# Schematics.net
KiCad netlist of a schematic drawn in Altium Designer
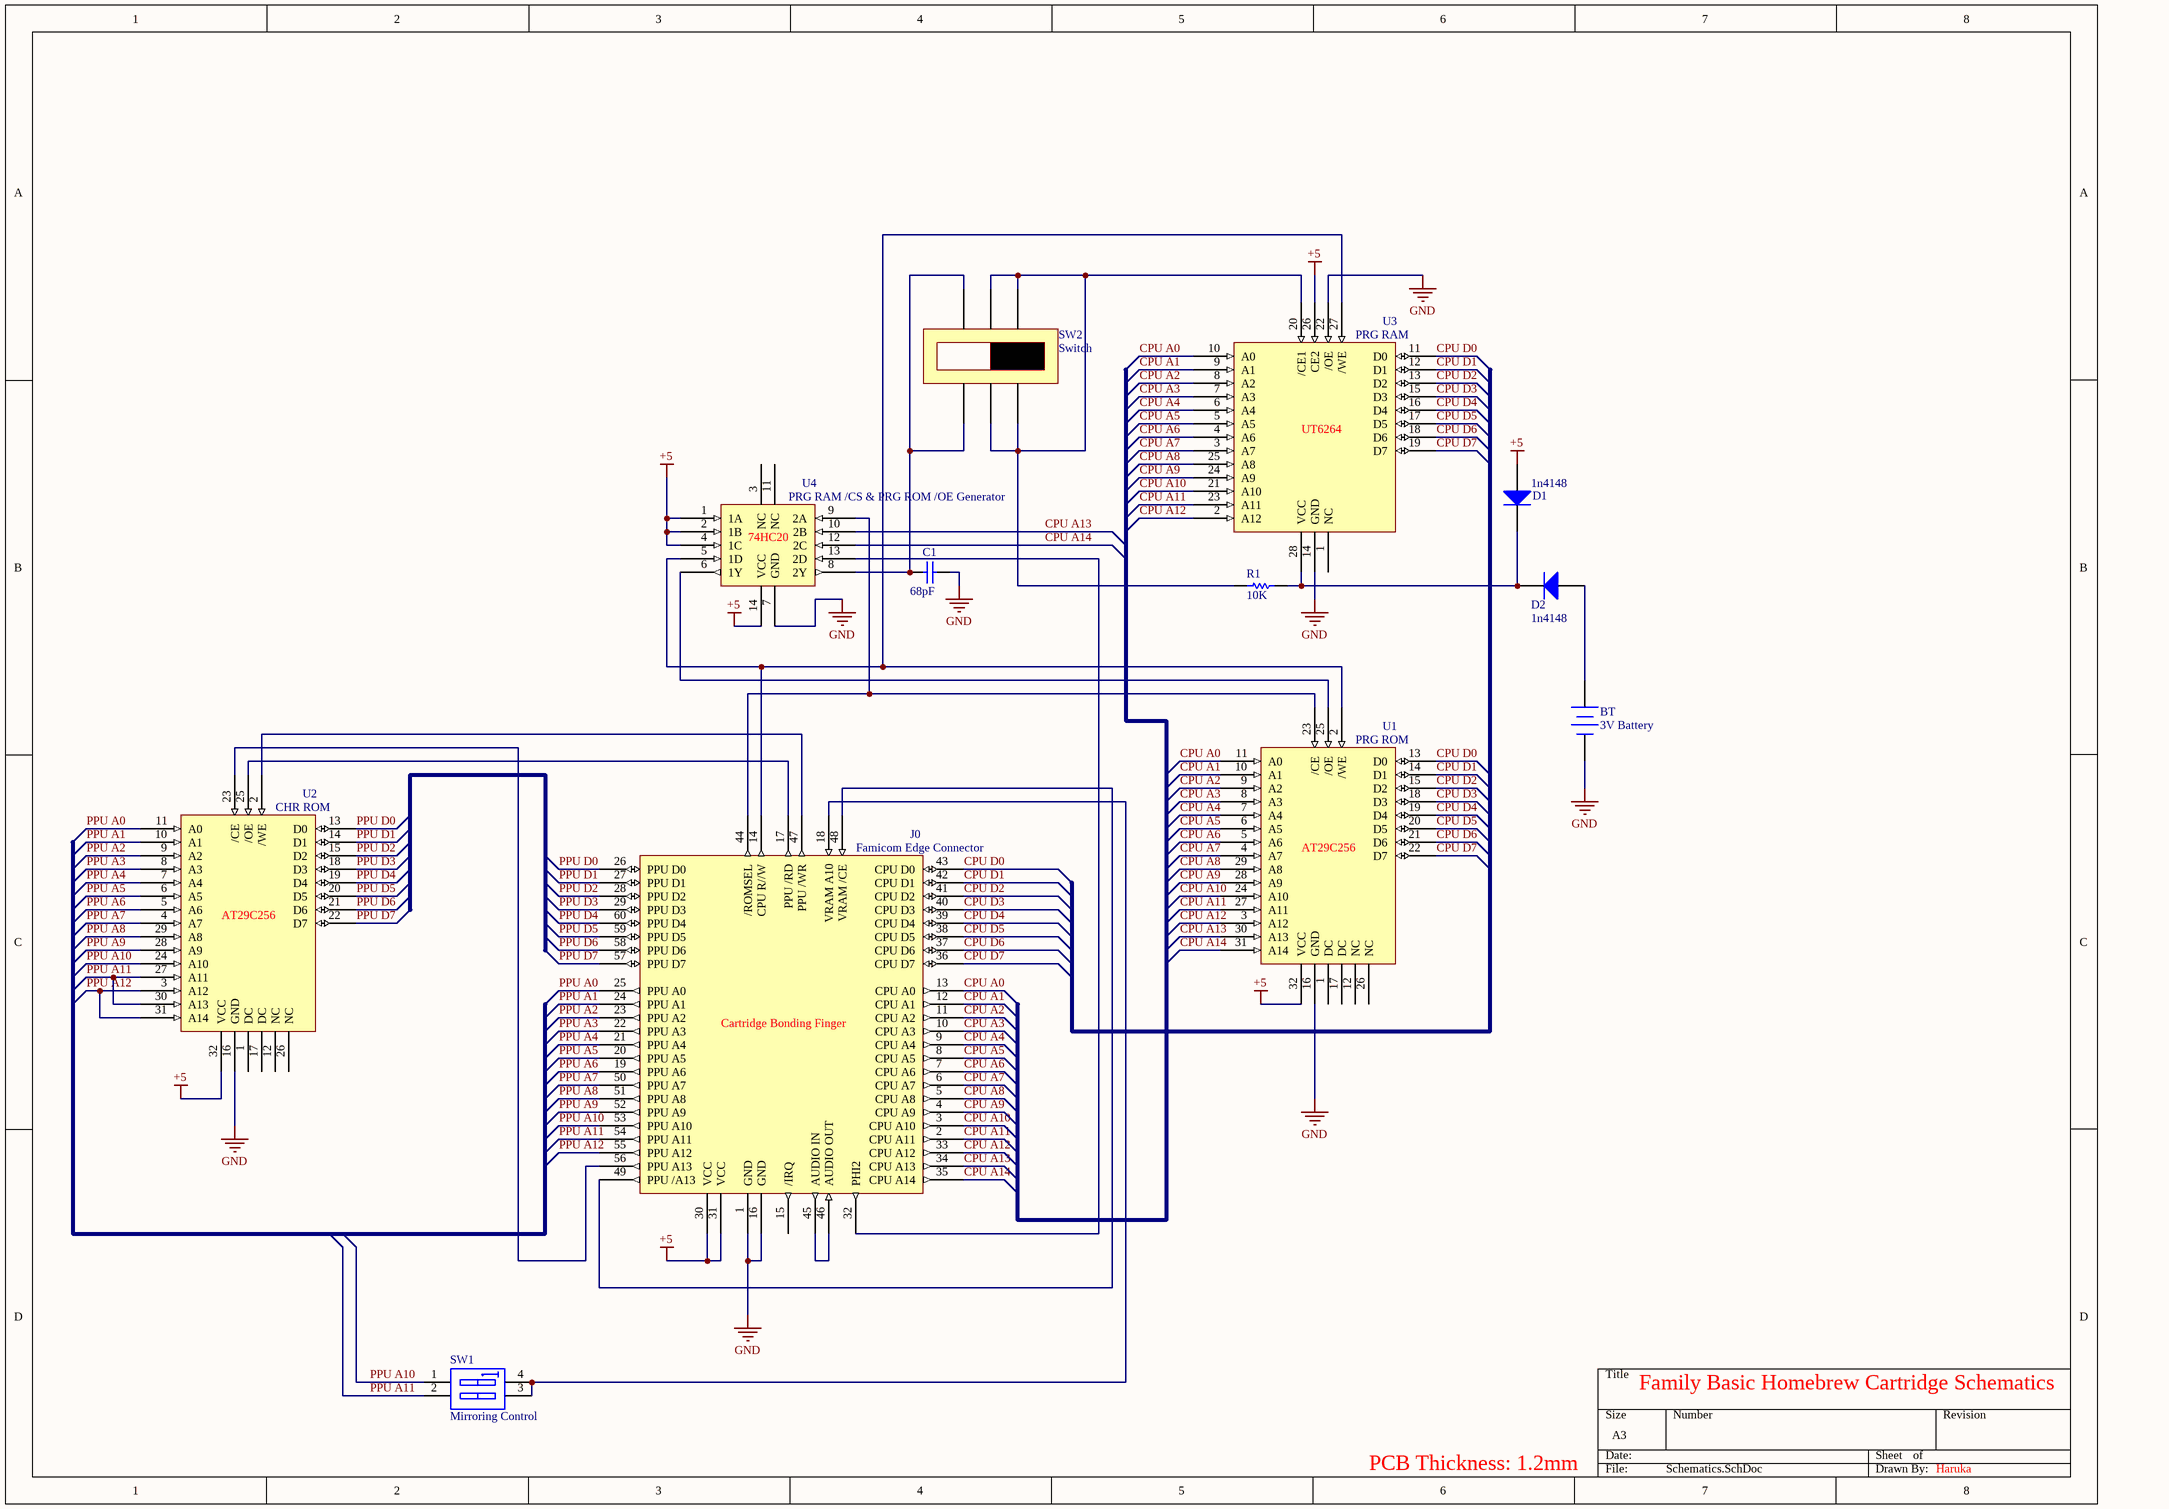
[diagram p0: Schematics.SchDoc]

(export (version "E")
  (design (tool "Eeschema 10.0.6"))
  (components
    (comp (ref "BT")
      (value "3V Battery")
      (footprint "BAT-2")
      (description "Multicell Battery")
      (fields (field (name "PUBLISHER") "Altium Limited"))
      (libsource (lib "Miscellaneous Devices") (part "Battery"))
    )
    (comp (ref "C1")
      (value "68pF")
      (footprint "C2512")
      (description "Capacitor (Semiconductor SIM Model)")
      (fields (field (name "Comment") "Cap Semi") (field (name "PUBLISHER") "Altium Limited"))
      (libsource (lib "Miscellaneous Devices") (part "Cap Semi"))
    )
    (comp (ref "D1")
      (value "1n4148")
      (footprint "DO-35")
      (description "High Conductance Fast Diode")
      (fields (field (name "PUBLISHER") "Altium Limited"))
      (libsource (lib "Miscellaneous Devices") (part "Diode 1N4148"))
    )
    (comp (ref "D2")
      (value "1n4148")
      (footprint "DO-35")
      (description "High Conductance Fast Diode")
      (fields (field (name "PUBLISHER") "Altium Limited"))
      (libsource (lib "Miscellaneous Devices") (part "Diode 1N4148"))
    )
    (comp (ref "J0")
      (value "Famicom Edge Connector")
      (footprint "CartridgeBondingFinger")
      (libsource (lib "CartridgeBondingFinger") (part "CartridgeBondingFinger"))
    )
    (comp (ref "R1")
      (value "10K")
      (footprint "AXIAL-0.3")
      (description "Resistor")
      (fields (field (name "Comment") "Res1") (field (name "PUBLISHER") "Altium Limited"))
      (libsource (lib "Miscellaneous Devices") (part "Res1"))
    )
    (comp (ref "SW1")
      (value "Mirroring Control")
      (footprint "DIP-4")
      (description "DIP Switch, 2 Position, SPST")
      (fields (field (name "PUBLISHER") "Altium Limited"))
      (libsource (lib "Miscellaneous Devices") (part "SW DIP-2"))
    )
    (comp (ref "SW2") (value "Switch") (footprint "DPDT-6") (libsource (lib "Discrete") (part "Switch")))
    (comp (ref "U1") (value "PRG ROM") (footprint "PLCC32") (libsource (lib "AT29C256") (part "AT29C256")))
    (comp (ref "U2") (value "CHR ROM") (footprint "PLCC32") (libsource (lib "AT29C256") (part "AT29C256")))
    (comp (ref "U3")
      (value "PRG RAM")
      (footprint "SOP127P1207-28N")
      (libsource (lib "UT6264") (part "UT6264"))
    )
    (comp (ref "U4")
      (value "PRG RAM /CS & PRG ROM /OE Generator")
      (footprint "SOP127P636-14N")
      (libsource (lib "74HC20") (part "74HC20"))
    )
  )
  (nets
    (net (code "1") (name "+5") (class "Default")
      (node (ref "D1") (pin "1") (pinfunction "A_1") (pintype "passive"))
      (node (ref "J0") (pin "30") (pinfunction "VCC_30") (pintype "power_in"))
      (node (ref "J0") (pin "31") (pinfunction "VCC_31") (pintype "power_in"))
      (node (ref "U1") (pin "32") (pinfunction "VCC_32") (pintype "power_in"))
      (node (ref "U2") (pin "32") (pinfunction "VCC_32") (pintype "power_in"))
      (node (ref "U3") (pin "26") (pinfunction "CE2_26") (pintype "input"))
      (node (ref "U4") (pin "1") (pinfunction "1A_1") (pintype "input"))
      (node (ref "U4") (pin "14") (pinfunction "VCC_14") (pintype "power_in"))
      (node (ref "U4") (pin "2") (pinfunction "1B_2") (pintype "input"))
      (node (ref "U4") (pin "4") (pinfunction "1C_4") (pintype "input"))
    )
    (net (code "2") (name "/CPU A0") (class "Default")
      (node (ref "J0") (pin "13") (pinfunction "CPU_A0_13") (pintype "output"))
      (node (ref "U1") (pin "11") (pinfunction "A0_11") (pintype "input"))
      (node (ref "U3") (pin "10") (pinfunction "A0_10") (pintype "input"))
    )
    (net (code "3") (name "/CPU A1") (class "Default")
      (node (ref "J0") (pin "12") (pinfunction "CPU_A1_12") (pintype "output"))
      (node (ref "U1") (pin "10") (pinfunction "A1_10") (pintype "input"))
      (node (ref "U3") (pin "9") (pinfunction "A1_9") (pintype "input"))
    )
    (net (code "4") (name "/CPU A2") (class "Default")
      (node (ref "J0") (pin "11") (pinfunction "CPU_A2_11") (pintype "output"))
      (node (ref "U1") (pin "9") (pinfunction "A2_9") (pintype "input"))
      (node (ref "U3") (pin "8") (pinfunction "A2_8") (pintype "input"))
    )
    (net (code "5") (name "/CPU A3") (class "Default")
      (node (ref "J0") (pin "10") (pinfunction "CPU_A3_10") (pintype "output"))
      (node (ref "U1") (pin "8") (pinfunction "A3_8") (pintype "input"))
      (node (ref "U3") (pin "7") (pinfunction "A3_7") (pintype "input"))
    )
    (net (code "6") (name "/CPU A4") (class "Default")
      (node (ref "J0") (pin "9") (pinfunction "CPU_A4_9") (pintype "output"))
      (node (ref "U1") (pin "7") (pinfunction "A4_7") (pintype "input"))
      (node (ref "U3") (pin "6") (pinfunction "A4_6") (pintype "input"))
    )
    (net (code "7") (name "/CPU A5") (class "Default")
      (node (ref "J0") (pin "8") (pinfunction "CPU_A5_8") (pintype "output"))
      (node (ref "U1") (pin "6") (pinfunction "A5_6") (pintype "input"))
      (node (ref "U3") (pin "5") (pinfunction "A5_5") (pintype "input"))
    )
    (net (code "8") (name "/CPU A6") (class "Default")
      (node (ref "J0") (pin "7") (pinfunction "CPU_A6_7") (pintype "output"))
      (node (ref "U1") (pin "5") (pinfunction "A6_5") (pintype "input"))
      (node (ref "U3") (pin "4") (pinfunction "A6_4") (pintype "input"))
    )
    (net (code "9") (name "/CPU A7") (class "Default")
      (node (ref "J0") (pin "6") (pinfunction "CPU_A7_6") (pintype "output"))
      (node (ref "U1") (pin "4") (pinfunction "A7_4") (pintype "input"))
      (node (ref "U3") (pin "3") (pinfunction "A7_3") (pintype "input"))
    )
    (net (code "10") (name "/CPU A8") (class "Default")
      (node (ref "J0") (pin "5") (pinfunction "CPU_A8_5") (pintype "output"))
      (node (ref "U1") (pin "29") (pinfunction "A8_29") (pintype "input"))
      (node (ref "U3") (pin "25") (pinfunction "A8_25") (pintype "input"))
    )
    (net (code "11") (name "/CPU A9") (class "Default")
      (node (ref "J0") (pin "4") (pinfunction "CPU_A9_4") (pintype "output"))
      (node (ref "U1") (pin "28") (pinfunction "A9_28") (pintype "input"))
      (node (ref "U3") (pin "24") (pinfunction "A9_24") (pintype "input"))
    )
    (net (code "12") (name "/CPU A10") (class "Default")
      (node (ref "J0") (pin "3") (pinfunction "CPU_A10_3") (pintype "output"))
      (node (ref "U1") (pin "24") (pinfunction "A10_24") (pintype "input"))
      (node (ref "U3") (pin "21") (pinfunction "A10_21") (pintype "input"))
    )
    (net (code "13") (name "/CPU A11") (class "Default")
      (node (ref "J0") (pin "2") (pinfunction "CPU_A11_2") (pintype "output"))
      (node (ref "U1") (pin "27") (pinfunction "A11_27") (pintype "input"))
      (node (ref "U3") (pin "23") (pinfunction "A11_23") (pintype "input"))
    )
    (net (code "14") (name "/CPU A12") (class "Default")
      (node (ref "J0") (pin "33") (pinfunction "CPU_A12_33") (pintype "output"))
      (node (ref "U1") (pin "3") (pinfunction "A12_3") (pintype "input"))
      (node (ref "U3") (pin "2") (pinfunction "A12_2") (pintype "input"))
    )
    (net (code "15") (name "/CPU A13") (class "Default")
      (node (ref "J0") (pin "34") (pinfunction "CPU_A13_34") (pintype "output"))
      (node (ref "U1") (pin "30") (pinfunction "A13_30") (pintype "input"))
      (node (ref "U4") (pin "10") (pinfunction "2B_10") (pintype "input"))
    )
    (net (code "16") (name "/CPU A14") (class "Default")
      (node (ref "J0") (pin "35") (pinfunction "CPU_A14_35") (pintype "output"))
      (node (ref "U1") (pin "31") (pinfunction "A14_31") (pintype "input"))
      (node (ref "U4") (pin "12") (pinfunction "2C_12") (pintype "input"))
    )
    (net (code "17") (name "/CPU D0") (class "Default")
      (node (ref "J0") (pin "43") (pinfunction "CPU_D0_43") (pintype "bidirectional"))
      (node (ref "U1") (pin "13") (pinfunction "D0_13") (pintype "bidirectional"))
      (node (ref "U3") (pin "11") (pinfunction "D0_11") (pintype "bidirectional"))
    )
    (net (code "18") (name "/CPU D1") (class "Default")
      (node (ref "J0") (pin "42") (pinfunction "CPU_D1_42") (pintype "bidirectional"))
      (node (ref "U1") (pin "14") (pinfunction "D1_14") (pintype "bidirectional"))
      (node (ref "U3") (pin "12") (pinfunction "D1_12") (pintype "bidirectional"))
    )
    (net (code "19") (name "/CPU D2") (class "Default")
      (node (ref "J0") (pin "41") (pinfunction "CPU_D2_41") (pintype "bidirectional"))
      (node (ref "U1") (pin "15") (pinfunction "D2_15") (pintype "bidirectional"))
      (node (ref "U3") (pin "13") (pinfunction "D2_13") (pintype "bidirectional"))
    )
    (net (code "20") (name "/CPU D3") (class "Default")
      (node (ref "J0") (pin "40") (pinfunction "CPU_D3_40") (pintype "bidirectional"))
      (node (ref "U1") (pin "18") (pinfunction "D3_18") (pintype "bidirectional"))
      (node (ref "U3") (pin "15") (pinfunction "D3_15") (pintype "bidirectional"))
    )
    (net (code "21") (name "/CPU D4") (class "Default")
      (node (ref "J0") (pin "39") (pinfunction "CPU_D4_39") (pintype "bidirectional"))
      (node (ref "U1") (pin "19") (pinfunction "D4_19") (pintype "bidirectional"))
      (node (ref "U3") (pin "16") (pinfunction "D4_16") (pintype "bidirectional"))
    )
    (net (code "22") (name "/CPU D5") (class "Default")
      (node (ref "J0") (pin "38") (pinfunction "CPU_D5_38") (pintype "bidirectional"))
      (node (ref "U1") (pin "20") (pinfunction "D5_20") (pintype "bidirectional"))
      (node (ref "U3") (pin "17") (pinfunction "D5_17") (pintype "bidirectional"))
    )
    (net (code "23") (name "/CPU D6") (class "Default")
      (node (ref "J0") (pin "37") (pinfunction "CPU_D6_37") (pintype "bidirectional"))
      (node (ref "U1") (pin "21") (pinfunction "D6_21") (pintype "bidirectional"))
      (node (ref "U3") (pin "18") (pinfunction "D6_18") (pintype "bidirectional"))
    )
    (net (code "24") (name "/CPU D7") (class "Default")
      (node (ref "J0") (pin "36") (pinfunction "CPU_D7_36") (pintype "bidirectional"))
      (node (ref "U1") (pin "22") (pinfunction "D7_22") (pintype "bidirectional"))
      (node (ref "U3") (pin "19") (pinfunction "D7_19") (pintype "bidirectional"))
    )
    (net (code "25") (name "/PPU A0") (class "Default")
      (node (ref "J0") (pin "25") (pinfunction "PPU_A0_25") (pintype "output"))
      (node (ref "U2") (pin "11") (pinfunction "A0_11") (pintype "input"))
    )
    (net (code "26") (name "/PPU A1") (class "Default")
      (node (ref "J0") (pin "24") (pinfunction "PPU_A1_24") (pintype "output"))
      (node (ref "U2") (pin "10") (pinfunction "A1_10") (pintype "input"))
    )
    (net (code "27") (name "/PPU A2") (class "Default")
      (node (ref "J0") (pin "23") (pinfunction "PPU_A2_23") (pintype "output"))
      (node (ref "U2") (pin "9") (pinfunction "A2_9") (pintype "input"))
    )
    (net (code "28") (name "/PPU A3") (class "Default")
      (node (ref "J0") (pin "22") (pinfunction "PPU_A3_22") (pintype "output"))
      (node (ref "U2") (pin "8") (pinfunction "A3_8") (pintype "input"))
    )
    (net (code "29") (name "/PPU A4") (class "Default")
      (node (ref "J0") (pin "21") (pinfunction "PPU_A4_21") (pintype "output"))
      (node (ref "U2") (pin "7") (pinfunction "A4_7") (pintype "input"))
    )
    (net (code "30") (name "/PPU A5") (class "Default")
      (node (ref "J0") (pin "20") (pinfunction "PPU_A5_20") (pintype "output"))
      (node (ref "U2") (pin "6") (pinfunction "A5_6") (pintype "input"))
    )
    (net (code "31") (name "/PPU A6") (class "Default")
      (node (ref "J0") (pin "19") (pinfunction "PPU_A6_19") (pintype "output"))
      (node (ref "U2") (pin "5") (pinfunction "A6_5") (pintype "input"))
    )
    (net (code "32") (name "/PPU A7") (class "Default")
      (node (ref "J0") (pin "50") (pinfunction "PPU_A7_50") (pintype "output"))
      (node (ref "U2") (pin "4") (pinfunction "A7_4") (pintype "input"))
    )
    (net (code "33") (name "/PPU A8") (class "Default")
      (node (ref "J0") (pin "51") (pinfunction "PPU_A8_51") (pintype "output"))
      (node (ref "U2") (pin "29") (pinfunction "A8_29") (pintype "input"))
    )
    (net (code "34") (name "/PPU A9") (class "Default")
      (node (ref "J0") (pin "52") (pinfunction "PPU_A9_52") (pintype "output"))
      (node (ref "U2") (pin "28") (pinfunction "A9_28") (pintype "input"))
    )
    (net (code "35") (name "/PPU A10") (class "Default")
      (node (ref "J0") (pin "53") (pinfunction "PPU_A10_53") (pintype "output"))
      (node (ref "SW1") (pin "1") (pinfunction "A1_1") (pintype "passive"))
      (node (ref "U2") (pin "24") (pinfunction "A10_24") (pintype "input"))
    )
    (net (code "36") (name "/PPU A11") (class "Default")
      (node (ref "J0") (pin "54") (pinfunction "PPU_A11_54") (pintype "output"))
      (node (ref "SW1") (pin "2") (pinfunction "A2_2") (pintype "passive"))
      (node (ref "U2") (pin "27") (pinfunction "A11_27") (pintype "input"))
      (node (ref "U2") (pin "30") (pinfunction "A13_30") (pintype "input"))
    )
    (net (code "37") (name "/PPU A12") (class "Default")
      (node (ref "J0") (pin "55") (pinfunction "PPU_A12_55") (pintype "output"))
      (node (ref "U2") (pin "3") (pinfunction "A12_3") (pintype "input"))
      (node (ref "U2") (pin "31") (pinfunction "A14_31") (pintype "input"))
    )
    (net (code "38") (name "/PPU D0") (class "Default")
      (node (ref "J0") (pin "26") (pinfunction "PPU_D0_26") (pintype "bidirectional"))
      (node (ref "U2") (pin "13") (pinfunction "D0_13") (pintype "bidirectional"))
    )
    (net (code "39") (name "/PPU D1") (class "Default")
      (node (ref "J0") (pin "27") (pinfunction "PPU_D1_27") (pintype "bidirectional"))
      (node (ref "U2") (pin "14") (pinfunction "D1_14") (pintype "bidirectional"))
    )
    (net (code "40") (name "/PPU D2") (class "Default")
      (node (ref "J0") (pin "28") (pinfunction "PPU_D2_28") (pintype "bidirectional"))
      (node (ref "U2") (pin "15") (pinfunction "D2_15") (pintype "bidirectional"))
    )
    (net (code "41") (name "/PPU D3") (class "Default")
      (node (ref "J0") (pin "29") (pinfunction "PPU_D3_29") (pintype "bidirectional"))
      (node (ref "U2") (pin "18") (pinfunction "D3_18") (pintype "bidirectional"))
    )
    (net (code "42") (name "/PPU D4") (class "Default")
      (node (ref "J0") (pin "60") (pinfunction "PPU_D4_60") (pintype "bidirectional"))
      (node (ref "U2") (pin "19") (pinfunction "D4_19") (pintype "bidirectional"))
    )
    (net (code "43") (name "/PPU D5") (class "Default")
      (node (ref "J0") (pin "59") (pinfunction "PPU_D5_59") (pintype "bidirectional"))
      (node (ref "U2") (pin "20") (pinfunction "D5_20") (pintype "bidirectional"))
    )
    (net (code "44") (name "/PPU D6") (class "Default")
      (node (ref "J0") (pin "58") (pinfunction "PPU_D6_58") (pintype "bidirectional"))
      (node (ref "U2") (pin "21") (pinfunction "D6_21") (pintype "bidirectional"))
    )
    (net (code "45") (name "/PPU D7") (class "Default")
      (node (ref "J0") (pin "57") (pinfunction "PPU_D7_57") (pintype "bidirectional"))
      (node (ref "U2") (pin "22") (pinfunction "D7_22") (pintype "bidirectional"))
    )
    (net (code "46") (name "GND") (class "Default")
      (node (ref "BT") (pin "2") (pinfunction "-_2") (pintype "passive"))
      (node (ref "C1") (pin "2") (pinfunction "2_2") (pintype "passive"))
      (node (ref "J0") (pin "1") (pinfunction "GND_1") (pintype "power_in"))
      (node (ref "J0") (pin "16") (pinfunction "GND_16") (pintype "power_in"))
      (node (ref "U1") (pin "16") (pinfunction "GND_16") (pintype "power_in"))
      (node (ref "U2") (pin "16") (pinfunction "GND_16") (pintype "power_in"))
      (node (ref "U3") (pin "14") (pinfunction "GND_14") (pintype "power_in"))
      (node (ref "U3") (pin "22") (pinfunction "/OE_22") (pintype "input"))
      (node (ref "U4") (pin "7") (pinfunction "GND_7") (pintype "power_in"))
    )
    (net (code "47") (name "Net-(BT-+)") (class "Default")
      (node (ref "BT") (pin "1") (pinfunction "+_1") (pintype "passive"))
      (node (ref "D2") (pin "1") (pinfunction "A_1") (pintype "passive"))
    )
    (net (code "48") (name "Net-(D1-K)") (class "Default")
      (node (ref "D1") (pin "2") (pinfunction "K_2") (pintype "passive"))
      (node (ref "D2") (pin "2") (pinfunction "K_2") (pintype "passive"))
      (node (ref "R1") (pin "1") (pinfunction "1_1") (pintype "passive"))
      (node (ref "U3") (pin "28") (pinfunction "VCC_28") (pintype "power_in"))
    )
    (net (code "49") (name "Net-(J0-AUDIO_IN)") (class "Default")
      (node (ref "J0") (pin "45") (pinfunction "AUDIO_IN_45") (pintype "output"))
      (node (ref "J0") (pin "46") (pinfunction "AUDIO_OUT_46") (pintype "input"))
    )
    (net (code "50") (name "Net-(J0-CPU_R{slash}{slash}W)") (class "Default")
      (node (ref "J0") (pin "14") (pinfunction "CPU_R//W_14") (pintype "output"))
      (node (ref "U1") (pin "2") (pinfunction "/WE_2") (pintype "input"))
      (node (ref "U3") (pin "27") (pinfunction "/WE_27") (pintype "input"))
      (node (ref "U4") (pin "5") (pinfunction "1D_5") (pintype "input"))
    )
    (net (code "51") (name "Net-(J0-PHI2)") (class "Default")
      (node (ref "J0") (pin "32") (pinfunction "PHI2_32") (pintype "output"))
      (node (ref "U4") (pin "13") (pinfunction "2D_13") (pintype "input"))
    )
    (net (code "52") (name "Net-(J0-PPU_A13)") (class "Default")
      (node (ref "J0") (pin "56") (pinfunction "PPU_A13_56") (pintype "output"))
      (node (ref "U2") (pin "23") (pinfunction "/CE_23") (pintype "input"))
    )
    (net (code "53") (name "Net-(J0-PPU_{slash}A13)") (class "Default")
      (node (ref "J0") (pin "48") (pinfunction "VRAM_/CE_48") (pintype "input"))
      (node (ref "J0") (pin "49") (pinfunction "PPU_/A13_49") (pintype "output"))
    )
    (net (code "54") (name "Net-(J0-PPU_{slash}RD)") (class "Default")
      (node (ref "J0") (pin "17") (pinfunction "PPU_/RD_17") (pintype "output"))
      (node (ref "U2") (pin "25") (pinfunction "/OE_25") (pintype "input"))
    )
    (net (code "55") (name "Net-(J0-PPU_{slash}WR)") (class "Default")
      (node (ref "J0") (pin "47") (pinfunction "PPU_/WR_47") (pintype "output"))
      (node (ref "U2") (pin "2") (pinfunction "/WE_2") (pintype "input"))
    )
    (net (code "56") (name "Net-(J0-VRAM_A10)") (class "Default")
      (node (ref "J0") (pin "18") (pinfunction "VRAM_A10_18") (pintype "input"))
      (node (ref "SW1") (pin "3") (pinfunction "B2_3") (pintype "passive"))
      (node (ref "SW1") (pin "4") (pinfunction "B1_4") (pintype "passive"))
    )
    (net (code "57") (name "Net-(J0-{slash}ROMSEL)") (class "Default")
      (node (ref "J0") (pin "44") (pinfunction "/ROMSEL_44") (pintype "output"))
      (node (ref "U1") (pin "23") (pinfunction "/CE_23") (pintype "input"))
      (node (ref "U4") (pin "9") (pinfunction "2A_9") (pintype "input"))
    )
    (net (code "58") (name "Net-(U1-{slash}OE)") (class "Default")
      (node (ref "U1") (pin "25") (pinfunction "/OE_25") (pintype "input"))
      (node (ref "U4") (pin "6") (pinfunction "1Y_6") (pintype "output"))
    )
    (net (code "59") (name "Net-(U3-{slash}CE1)") (class "Default")
      (node (ref "R1") (pin "2") (pinfunction "2_2") (pintype "passive"))
      (node (ref "SW2") (pin "SWITCH_B1") (pinfunction "SWITCH_B1_SWITCH_B1") (pintype "passive"))
      (node (ref "SW2") (pin "SWITCH_B2") (pinfunction "SWITCH_B2_SWITCH_B2") (pintype "passive"))
      (node (ref "SW2") (pin "SWITCH_C1") (pinfunction "SWITCH_C1_SWITCH_C1") (pintype "passive"))
      (node (ref "SW2") (pin "SWITCH_C2") (pinfunction "SWITCH_C2_SWITCH_C2") (pintype "passive"))
      (node (ref "U3") (pin "20") (pinfunction "/CE1_20") (pintype "input"))
    )
    (net (code "60") (name "Net-(U4-2Y)") (class "Default")
      (node (ref "C1") (pin "1") (pinfunction "1_1") (pintype "passive"))
      (node (ref "SW2") (pin "SWITCH_A1") (pinfunction "SWITCH_A1_SWITCH_A1") (pintype "passive"))
      (node (ref "SW2") (pin "SWITCH_A2") (pinfunction "SWITCH_A2_SWITCH_A2") (pintype "passive"))
      (node (ref "U4") (pin "8") (pinfunction "2Y_8") (pintype "output"))
    )
    (net (code "61") (name "unconnected-(J0-{slash}IRQ-Pad15)") (class "Default")
      (node (ref "J0") (pin "15") (pinfunction "/IRQ_15") (pintype "output"))
    )
    (net (code "62") (name "unconnected-(U1-DC-Pad1)") (class "Default")
      (node (ref "U1") (pin "1") (pinfunction "DC_1") (pintype "passive"))
    )
    (net (code "63") (name "unconnected-(U1-DC-Pad17)") (class "Default")
      (node (ref "U1") (pin "17") (pinfunction "DC_17") (pintype "passive"))
    )
    (net (code "64") (name "unconnected-(U1-NC-Pad12)") (class "Default")
      (node (ref "U1") (pin "12") (pinfunction "NC_12") (pintype "passive"))
    )
    (net (code "65") (name "unconnected-(U1-NC-Pad26)") (class "Default")
      (node (ref "U1") (pin "26") (pinfunction "NC_26") (pintype "passive"))
    )
    (net (code "66") (name "unconnected-(U2-DC-Pad1)") (class "Default")
      (node (ref "U2") (pin "1") (pinfunction "DC_1") (pintype "passive"))
    )
    (net (code "67") (name "unconnected-(U2-DC-Pad17)") (class "Default")
      (node (ref "U2") (pin "17") (pinfunction "DC_17") (pintype "passive"))
    )
    (net (code "68") (name "unconnected-(U2-NC-Pad12)") (class "Default")
      (node (ref "U2") (pin "12") (pinfunction "NC_12") (pintype "passive"))
    )
    (net (code "69") (name "unconnected-(U2-NC-Pad26)") (class "Default")
      (node (ref "U2") (pin "26") (pinfunction "NC_26") (pintype "passive"))
    )
    (net (code "70") (name "unconnected-(U3-NC-Pad1)") (class "Default")
      (node (ref "U3") (pin "1") (pinfunction "NC_1") (pintype "passive"))
    )
    (net (code "71") (name "unconnected-(U4-NC-Pad3)") (class "Default")
      (node (ref "U4") (pin "3") (pinfunction "NC_3") (pintype "passive"))
    )
    (net (code "72") (name "unconnected-(U4-NC-Pad11)") (class "Default")
      (node (ref "U4") (pin "11") (pinfunction "NC_11") (pintype "passive"))
    )
  )
)
